# Schematic.net
KiCad netlist of a schematic drawn in Altium Designer
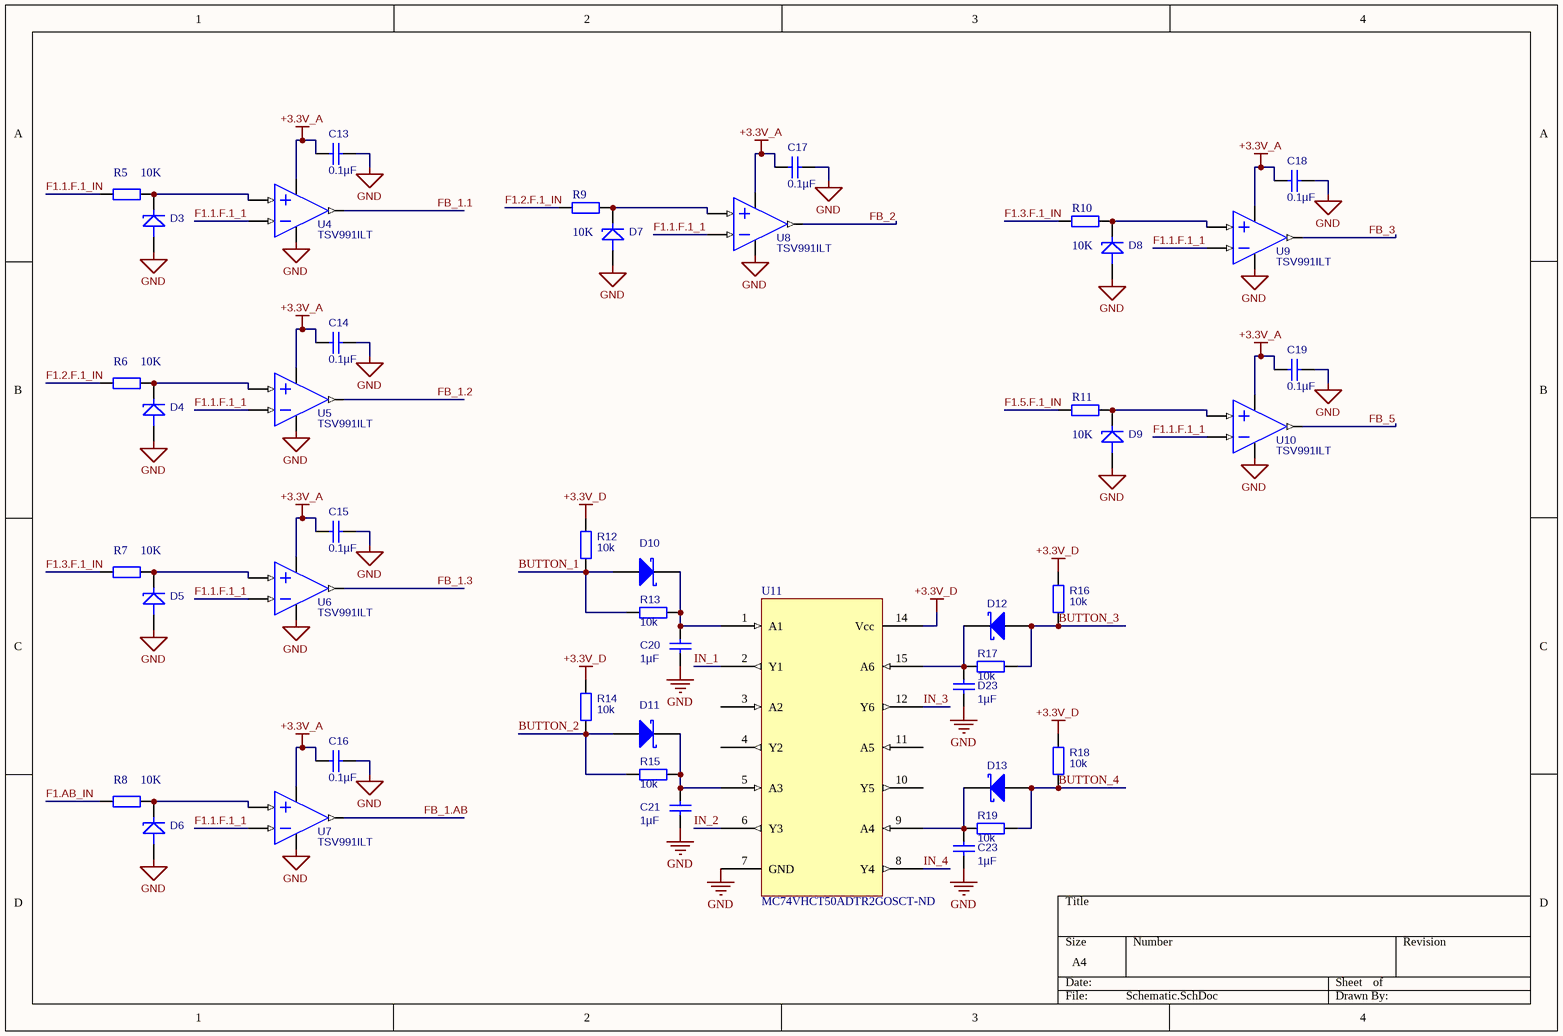
[diagram p0: Schematic.SchDoc]

(export (version "E")
  (design (tool "Eeschema 10.0.6"))
  (components
    (comp (ref "C13")
      (value "0.1µF")
      (footprint "TDK C-Series (1608)")
      (description "Capacitor")
      (fields (field (name "PUBLISHER") "Altium Limited"))
      (libsource (lib "Miscellaneous Devices") (part "Cap"))
    )
    (comp (ref "C14")
      (value "0.1µF")
      (footprint "TDK C-Series (1608)")
      (description "Capacitor")
      (fields (field (name "PUBLISHER") "Altium Limited"))
      (libsource (lib "Miscellaneous Devices") (part "Cap"))
    )
    (comp (ref "C15")
      (value "0.1µF")
      (footprint "TDK C-Series (1608)")
      (description "Capacitor")
      (fields (field (name "PUBLISHER") "Altium Limited"))
      (libsource (lib "Miscellaneous Devices") (part "Cap"))
    )
    (comp (ref "C16")
      (value "0.1µF")
      (footprint "TDK C-Series (1608)")
      (description "Capacitor")
      (fields (field (name "PUBLISHER") "Altium Limited"))
      (libsource (lib "Miscellaneous Devices") (part "Cap"))
    )
    (comp (ref "C17")
      (value "0.1µF")
      (footprint "TDK C-Series (1608)")
      (description "Capacitor")
      (fields (field (name "PUBLISHER") "Altium Limited"))
      (libsource (lib "Miscellaneous Devices") (part "Cap"))
    )
    (comp (ref "C18")
      (value "0.1µF")
      (footprint "TDK C-Series (1608)")
      (description "Capacitor")
      (fields (field (name "PUBLISHER") "Altium Limited"))
      (libsource (lib "Miscellaneous Devices") (part "Cap"))
    )
    (comp (ref "C19")
      (value "0.1µF")
      (footprint "TDK C-Series (1608)")
      (description "Capacitor")
      (fields (field (name "PUBLISHER") "Altium Limited"))
      (libsource (lib "Miscellaneous Devices") (part "Cap"))
    )
    (comp (ref "C20")
      (value "1µF")
      (footprint "TDK C-Series (1608)")
      (description "Capacitor")
      (fields (field (name "Comment") "Cap") (field (name "PUBLISHER") "Altium Limited"))
      (libsource (lib "Miscellaneous Devices") (part "Cap"))
    )
    (comp (ref "C21")
      (value "1µF")
      (footprint "TDK C-Series (1608)")
      (description "Capacitor")
      (fields (field (name "Comment") "Cap") (field (name "PUBLISHER") "Altium Limited"))
      (libsource (lib "Miscellaneous Devices") (part "Cap"))
    )
    (comp (ref "C23")
      (value "1µF")
      (footprint "TDK C-Series (1608)")
      (description "Capacitor")
      (fields (field (name "Comment") "Cap") (field (name "PUBLISHER") "Altium Limited"))
      (libsource (lib "Miscellaneous Devices") (part "Cap"))
    )
    (comp (ref "D3")
      (value "PTVSxS1UR-Series")
      (footprint "NXP PTVSxS1UR-Series (SOD123W)")
      (description "400W TVS Diode")
      (libsource (lib "FSM_2017") (part "NXP PTVSxS1UR-Series"))
    )
    (comp (ref "D4")
      (value "PTVSxS1UR-Series")
      (footprint "NXP PTVSxS1UR-Series (SOD123W)")
      (description "400W TVS Diode")
      (libsource (lib "FSM_2017") (part "NXP PTVSxS1UR-Series"))
    )
    (comp (ref "D5")
      (value "PTVSxS1UR-Series")
      (footprint "NXP PTVSxS1UR-Series (SOD123W)")
      (description "400W TVS Diode")
      (libsource (lib "FSM_2017") (part "NXP PTVSxS1UR-Series"))
    )
    (comp (ref "D6")
      (value "PTVSxS1UR-Series")
      (footprint "NXP PTVSxS1UR-Series (SOD123W)")
      (description "400W TVS Diode")
      (libsource (lib "FSM_2017") (part "NXP PTVSxS1UR-Series"))
    )
    (comp (ref "D7")
      (value "PTVSxS1UR-Series")
      (footprint "NXP PTVSxS1UR-Series (SOD123W)")
      (description "400W TVS Diode")
      (libsource (lib "FSM_2017") (part "NXP PTVSxS1UR-Series"))
    )
    (comp (ref "D8")
      (value "PTVSxS1UR-Series")
      (footprint "NXP PTVSxS1UR-Series (SOD123W)")
      (description "400W TVS Diode")
      (libsource (lib "FSM_2017") (part "NXP PTVSxS1UR-Series"))
    )
    (comp (ref "D9")
      (value "PTVSxS1UR-Series")
      (footprint "NXP PTVSxS1UR-Series (SOD123W)")
      (description "400W TVS Diode")
      (libsource (lib "FSM_2017") (part "NXP PTVSxS1UR-Series"))
    )
    (comp (ref "D10")
      (value "D Schottky")
      (footprint "NXP PMEG6020AELRX (SOD-123)")
      (description "Schottky Diode")
      (fields (field (name "PUBLISHER") "Altium Limited"))
      (libsource (lib "Miscellaneous Devices") (part "D Schottky"))
    )
    (comp (ref "D11")
      (value "D Schottky")
      (footprint "NXP PMEG6020AELRX (SOD-123)")
      (description "Schottky Diode")
      (fields (field (name "PUBLISHER") "Altium Limited"))
      (libsource (lib "Miscellaneous Devices") (part "D Schottky"))
    )
    (comp (ref "D12")
      (value "D Schottky")
      (footprint "NXP PMEG6020AELRX (SOD-123)")
      (description "Schottky Diode")
      (fields (field (name "PUBLISHER") "Altium Limited"))
      (libsource (lib "Miscellaneous Devices") (part "D Schottky"))
    )
    (comp (ref "D13")
      (value "D Schottky")
      (footprint "NXP PMEG6020AELRX (SOD-123)")
      (description "Schottky Diode")
      (fields (field (name "PUBLISHER") "Altium Limited"))
      (libsource (lib "Miscellaneous Devices") (part "D Schottky"))
    )
    (comp (ref "D23")
      (value "1µF")
      (footprint "TDK C-Series (1608)")
      (description "Capacitor")
      (fields (field (name "Comment") "Cap") (field (name "PUBLISHER") "Altium Limited"))
      (libsource (lib "Miscellaneous Devices") (part "Cap"))
    )
    (comp (ref "R5")
      (value "10K")
      (footprint "AXIAL-0.4")
      (description "Resistor")
      (fields (field (name "PUBLISHER") "Altium Limited"))
      (libsource (lib "Miscellaneous Devices") (part "Res2"))
    )
    (comp (ref "R6")
      (value "10K")
      (footprint "AXIAL-0.4")
      (description "Resistor")
      (fields (field (name "PUBLISHER") "Altium Limited"))
      (libsource (lib "Miscellaneous Devices") (part "Res2"))
    )
    (comp (ref "R7")
      (value "10K")
      (footprint "AXIAL-0.4")
      (description "Resistor")
      (fields (field (name "PUBLISHER") "Altium Limited"))
      (libsource (lib "Miscellaneous Devices") (part "Res2"))
    )
    (comp (ref "R8")
      (value "10K")
      (footprint "AXIAL-0.4")
      (description "Resistor")
      (fields (field (name "PUBLISHER") "Altium Limited"))
      (libsource (lib "Miscellaneous Devices") (part "Res2"))
    )
    (comp (ref "R9")
      (value "10K")
      (footprint "AXIAL-0.4")
      (description "Resistor")
      (fields (field (name "PUBLISHER") "Altium Limited"))
      (libsource (lib "Miscellaneous Devices") (part "Res2"))
    )
    (comp (ref "R10")
      (value "10K")
      (footprint "AXIAL-0.4")
      (description "Resistor")
      (fields (field (name "PUBLISHER") "Altium Limited"))
      (libsource (lib "Miscellaneous Devices") (part "Res2"))
    )
    (comp (ref "R11")
      (value "10K")
      (footprint "AXIAL-0.4")
      (description "Resistor")
      (fields (field (name "PUBLISHER") "Altium Limited"))
      (libsource (lib "Miscellaneous Devices") (part "Res2"))
    )
    (comp (ref "R12")
      (value "10k")
      (footprint "Panasonic ERJ-Series (1608)")
      (description "Resistor")
      (fields (field (name "PUBLISHER") "Altium Limited"))
      (libsource (lib "Miscellaneous Devices") (part "Res2"))
    )
    (comp (ref "R13")
      (value "10k")
      (footprint "Panasonic ERJ-Series (1608)")
      (description "Resistor")
      (fields (field (name "PUBLISHER") "Altium Limited"))
      (libsource (lib "") (part "Res2_1"))
    )
    (comp (ref "R14")
      (value "10k")
      (footprint "Panasonic ERJ-Series (1608)")
      (description "Resistor")
      (fields (field (name "PUBLISHER") "Altium Limited"))
      (libsource (lib "Miscellaneous Devices") (part "Res2"))
    )
    (comp (ref "R15")
      (value "10k")
      (footprint "Panasonic ERJ-Series (1608)")
      (description "Resistor")
      (fields (field (name "PUBLISHER") "Altium Limited"))
      (libsource (lib "") (part "Res2_1"))
    )
    (comp (ref "R16")
      (value "10k")
      (footprint "Panasonic ERJ-Series (1608)")
      (description "Resistor")
      (fields (field (name "PUBLISHER") "Altium Limited"))
      (libsource (lib "Miscellaneous Devices") (part "Res2"))
    )
    (comp (ref "R17")
      (value "10k")
      (footprint "Panasonic ERJ-Series (1608)")
      (description "Resistor")
      (fields (field (name "PUBLISHER") "Altium Limited"))
      (libsource (lib "") (part "Res2_1"))
    )
    (comp (ref "R18")
      (value "10k")
      (footprint "Panasonic ERJ-Series (1608)")
      (description "Resistor")
      (fields (field (name "PUBLISHER") "Altium Limited"))
      (libsource (lib "Miscellaneous Devices") (part "Res2"))
    )
    (comp (ref "R19")
      (value "10k")
      (footprint "Panasonic ERJ-Series (1608)")
      (description "Resistor")
      (fields (field (name "PUBLISHER") "Altium Limited"))
      (libsource (lib "") (part "Res2_1"))
    )
    (comp (ref "U4")
      (value "TSV991ILT")
      (footprint "STMicroelectronics TSV991ILT (SOT-23-5)")
      (description "20MHz Op-Amp")
      (libsource (lib "FSM_2017") (part "STMicroelectronics TSV991ILT"))
    )
    (comp (ref "U5")
      (value "TSV991ILT")
      (footprint "STMicroelectronics TSV991ILT (SOT-23-5)")
      (description "20MHz Op-Amp")
      (libsource (lib "FSM_2017") (part "STMicroelectronics TSV991ILT"))
    )
    (comp (ref "U6")
      (value "TSV991ILT")
      (footprint "STMicroelectronics TSV991ILT (SOT-23-5)")
      (description "20MHz Op-Amp")
      (libsource (lib "FSM_2017") (part "STMicroelectronics TSV991ILT"))
    )
    (comp (ref "U7")
      (value "TSV991ILT")
      (footprint "STMicroelectronics TSV991ILT (SOT-23-5)")
      (description "20MHz Op-Amp")
      (libsource (lib "FSM_2017") (part "STMicroelectronics TSV991ILT"))
    )
    (comp (ref "U8")
      (value "TSV991ILT")
      (footprint "STMicroelectronics TSV991ILT (SOT-23-5)")
      (description "20MHz Op-Amp")
      (libsource (lib "FSM_2017") (part "STMicroelectronics TSV991ILT"))
    )
    (comp (ref "U9")
      (value "TSV991ILT")
      (footprint "STMicroelectronics TSV991ILT (SOT-23-5)")
      (description "20MHz Op-Amp")
      (libsource (lib "FSM_2017") (part "STMicroelectronics TSV991ILT"))
    )
    (comp (ref "U10")
      (value "TSV991ILT")
      (footprint "STMicroelectronics TSV991ILT (SOT-23-5)")
      (description "20MHz Op-Amp")
      (libsource (lib "FSM_2017") (part "STMicroelectronics TSV991ILT"))
    )
    (comp (ref "U11")
      (value "MC74VHCT50A")
      (description "6-Channel CMOS Buffer")
      (fields (field (name "SUPPLIER PART NUMBER 1") "MC74VHCT50ADTR2GOSCT-ND"))
      (libsource (lib "Schematics Library") (part "MC74VHCT50A"))
    )
  )
  (nets
    (net (code "1") (name "+3.3V_A") (class "Default")
      (node (ref "C13") (pin "2") (pinfunction "2_2") (pintype "passive"))
      (node (ref "C14") (pin "2") (pinfunction "2_2") (pintype "passive"))
      (node (ref "C15") (pin "2") (pinfunction "2_2") (pintype "passive"))
      (node (ref "C16") (pin "2") (pinfunction "2_2") (pintype "passive"))
      (node (ref "C17") (pin "2") (pinfunction "2_2") (pintype "passive"))
      (node (ref "C18") (pin "2") (pinfunction "2_2") (pintype "passive"))
      (node (ref "C19") (pin "2") (pinfunction "2_2") (pintype "passive"))
      (node (ref "U10") (pin "5") (pinfunction "VCC+_5") (pintype "power_in"))
      (node (ref "U4") (pin "5") (pinfunction "VCC+_5") (pintype "power_in"))
      (node (ref "U5") (pin "5") (pinfunction "VCC+_5") (pintype "power_in"))
      (node (ref "U6") (pin "5") (pinfunction "VCC+_5") (pintype "power_in"))
      (node (ref "U7") (pin "5") (pinfunction "VCC+_5") (pintype "power_in"))
      (node (ref "U8") (pin "5") (pinfunction "VCC+_5") (pintype "power_in"))
      (node (ref "U9") (pin "5") (pinfunction "VCC+_5") (pintype "power_in"))
    )
    (net (code "2") (name "+3.3V_D") (class "Default")
      (node (ref "R12") (pin "1") (pinfunction "1_1") (pintype "passive"))
      (node (ref "R14") (pin "1") (pinfunction "1_1") (pintype "passive"))
      (node (ref "R16") (pin "1") (pinfunction "1_1") (pintype "passive"))
      (node (ref "R18") (pin "1") (pinfunction "1_1") (pintype "passive"))
      (node (ref "U11") (pin "14") (pinfunction "Vcc_14") (pintype "power_in"))
    )
    (net (code "3") (name "/BUTTON_1") (class "Default")
      (node (ref "D10") (pin "1") (pinfunction "A_1") (pintype "passive"))
      (node (ref "R12") (pin "2") (pinfunction "2_2") (pintype "passive"))
      (node (ref "R13") (pin "1") (pinfunction "1_1") (pintype "passive"))
    )
    (net (code "4") (name "/BUTTON_2") (class "Default")
      (node (ref "D11") (pin "1") (pinfunction "A_1") (pintype "passive"))
      (node (ref "R14") (pin "2") (pinfunction "2_2") (pintype "passive"))
      (node (ref "R15") (pin "1") (pinfunction "1_1") (pintype "passive"))
    )
    (net (code "5") (name "/BUTTON_3") (class "Default")
      (node (ref "D12") (pin "1") (pinfunction "A_1") (pintype "passive"))
      (node (ref "R16") (pin "2") (pinfunction "2_2") (pintype "passive"))
      (node (ref "R17") (pin "2") (pinfunction "2_2") (pintype "passive"))
    )
    (net (code "6") (name "/BUTTON_4") (class "Default")
      (node (ref "D13") (pin "1") (pinfunction "A_1") (pintype "passive"))
      (node (ref "R18") (pin "2") (pinfunction "2_2") (pintype "passive"))
      (node (ref "R19") (pin "2") (pinfunction "2_2") (pintype "passive"))
    )
    (net (code "7") (name "/F1.1.F.1_1") (class "Default")
      (node (ref "U10") (pin "4") (pinfunction "IN-_4") (pintype "input"))
      (node (ref "U4") (pin "4") (pinfunction "IN-_4") (pintype "input"))
      (node (ref "U5") (pin "4") (pinfunction "IN-_4") (pintype "input"))
      (node (ref "U6") (pin "4") (pinfunction "IN-_4") (pintype "input"))
      (node (ref "U7") (pin "4") (pinfunction "IN-_4") (pintype "input"))
      (node (ref "U8") (pin "4") (pinfunction "IN-_4") (pintype "input"))
      (node (ref "U9") (pin "4") (pinfunction "IN-_4") (pintype "input"))
    )
    (net (code "8") (name "/F1.1.F.1_IN") (class "Default")
      (node (ref "R5") (pin "2") (pinfunction "2_2") (pintype "passive"))
    )
    (net (code "9") (name "/F1.2.F.1_IN") (class "Default")
      (node (ref "R6") (pin "2") (pinfunction "2_2") (pintype "passive"))
      (node (ref "R9") (pin "2") (pinfunction "2_2") (pintype "passive"))
    )
    (net (code "10") (name "/F1.3.F.1_IN") (class "Default")
      (node (ref "R10") (pin "2") (pinfunction "2_2") (pintype "passive"))
      (node (ref "R7") (pin "2") (pinfunction "2_2") (pintype "passive"))
    )
    (net (code "11") (name "/F1.5.F.1_IN") (class "Default")
      (node (ref "R11") (pin "2") (pinfunction "2_2") (pintype "passive"))
    )
    (net (code "12") (name "/F1.AB_IN") (class "Default")
      (node (ref "R8") (pin "2") (pinfunction "2_2") (pintype "passive"))
    )
    (net (code "13") (name "/FB_1.1") (class "Default")
      (node (ref "U4") (pin "1") (pinfunction "OUT_1") (pintype "output"))
    )
    (net (code "14") (name "/FB_1.2") (class "Default")
      (node (ref "U5") (pin "1") (pinfunction "OUT_1") (pintype "output"))
    )
    (net (code "15") (name "/FB_1.3") (class "Default")
      (node (ref "U6") (pin "1") (pinfunction "OUT_1") (pintype "output"))
    )
    (net (code "16") (name "/FB_1.AB") (class "Default")
      (node (ref "U7") (pin "1") (pinfunction "OUT_1") (pintype "output"))
    )
    (net (code "17") (name "/FB_2") (class "Default")
      (node (ref "U8") (pin "1") (pinfunction "OUT_1") (pintype "output"))
    )
    (net (code "18") (name "/FB_3") (class "Default")
      (node (ref "U9") (pin "1") (pinfunction "OUT_1") (pintype "output"))
    )
    (net (code "19") (name "/FB_5") (class "Default")
      (node (ref "U10") (pin "1") (pinfunction "OUT_1") (pintype "output"))
    )
    (net (code "20") (name "/IN_1") (class "Default")
      (node (ref "U11") (pin "2") (pinfunction "Y1_2") (pintype "output"))
    )
    (net (code "21") (name "/IN_2") (class "Default")
      (node (ref "U11") (pin "6") (pinfunction "Y3_6") (pintype "output"))
    )
    (net (code "22") (name "/IN_3") (class "Default")
      (node (ref "U11") (pin "12") (pinfunction "Y6_12") (pintype "output"))
    )
    (net (code "23") (name "/IN_4") (class "Default")
      (node (ref "U11") (pin "8") (pinfunction "Y4_8") (pintype "output"))
    )
    (net (code "24") (name "GND") (class "Default")
      (node (ref "C13") (pin "1") (pinfunction "1_1") (pintype "passive"))
      (node (ref "C14") (pin "1") (pinfunction "1_1") (pintype "passive"))
      (node (ref "C15") (pin "1") (pinfunction "1_1") (pintype "passive"))
      (node (ref "C16") (pin "1") (pinfunction "1_1") (pintype "passive"))
      (node (ref "C17") (pin "1") (pinfunction "1_1") (pintype "passive"))
      (node (ref "C18") (pin "1") (pinfunction "1_1") (pintype "passive"))
      (node (ref "C19") (pin "1") (pinfunction "1_1") (pintype "passive"))
      (node (ref "C20") (pin "1") (pinfunction "1_1") (pintype "passive"))
      (node (ref "C21") (pin "1") (pinfunction "1_1") (pintype "passive"))
      (node (ref "C23") (pin "1") (pinfunction "1_1") (pintype "passive"))
      (node (ref "D23") (pin "1") (pinfunction "1_1") (pintype "passive"))
      (node (ref "D3") (pin "2") (pinfunction "2_2") (pintype "passive"))
      (node (ref "D4") (pin "2") (pinfunction "2_2") (pintype "passive"))
      (node (ref "D5") (pin "2") (pinfunction "2_2") (pintype "passive"))
      (node (ref "D6") (pin "2") (pinfunction "2_2") (pintype "passive"))
      (node (ref "D7") (pin "2") (pinfunction "2_2") (pintype "passive"))
      (node (ref "D8") (pin "2") (pinfunction "2_2") (pintype "passive"))
      (node (ref "D9") (pin "2") (pinfunction "2_2") (pintype "passive"))
      (node (ref "U10") (pin "2") (pinfunction "VCC-_2") (pintype "power_in"))
      (node (ref "U11") (pin "7") (pinfunction "GND_7") (pintype "passive"))
      (node (ref "U4") (pin "2") (pinfunction "VCC-_2") (pintype "power_in"))
      (node (ref "U5") (pin "2") (pinfunction "VCC-_2") (pintype "power_in"))
      (node (ref "U6") (pin "2") (pinfunction "VCC-_2") (pintype "power_in"))
      (node (ref "U7") (pin "2") (pinfunction "VCC-_2") (pintype "power_in"))
      (node (ref "U8") (pin "2") (pinfunction "VCC-_2") (pintype "power_in"))
      (node (ref "U9") (pin "2") (pinfunction "VCC-_2") (pintype "power_in"))
    )
    (net (code "25") (name "Net-(D10-K)") (class "Default")
      (node (ref "C20") (pin "2") (pinfunction "2_2") (pintype "passive"))
      (node (ref "D10") (pin "2") (pinfunction "K_2") (pintype "passive"))
      (node (ref "R13") (pin "2") (pinfunction "2_2") (pintype "passive"))
      (node (ref "U11") (pin "1") (pinfunction "A1_1") (pintype "input"))
    )
    (net (code "26") (name "Net-(D11-K)") (class "Default")
      (node (ref "C21") (pin "2") (pinfunction "2_2") (pintype "passive"))
      (node (ref "D11") (pin "2") (pinfunction "K_2") (pintype "passive"))
      (node (ref "R15") (pin "2") (pinfunction "2_2") (pintype "passive"))
      (node (ref "U11") (pin "5") (pinfunction "A3_5") (pintype "input"))
    )
    (net (code "27") (name "Net-(D12-K)") (class "Default")
      (node (ref "D12") (pin "2") (pinfunction "K_2") (pintype "passive"))
      (node (ref "D23") (pin "2") (pinfunction "2_2") (pintype "passive"))
      (node (ref "R17") (pin "1") (pinfunction "1_1") (pintype "passive"))
      (node (ref "U11") (pin "15") (pinfunction "A6_15") (pintype "input"))
    )
    (net (code "28") (name "Net-(D13-K)") (class "Default")
      (node (ref "C23") (pin "2") (pinfunction "2_2") (pintype "passive"))
      (node (ref "D13") (pin "2") (pinfunction "K_2") (pintype "passive"))
      (node (ref "R19") (pin "1") (pinfunction "1_1") (pintype "passive"))
      (node (ref "U11") (pin "9") (pinfunction "A4_9") (pintype "input"))
    )
    (net (code "29") (name "Net-(U4-IN+)") (class "Default")
      (node (ref "D3") (pin "1") (pinfunction "1_1") (pintype "passive"))
      (node (ref "R5") (pin "1") (pinfunction "1_1") (pintype "passive"))
      (node (ref "U4") (pin "3") (pinfunction "IN+_3") (pintype "input"))
    )
    (net (code "30") (name "Net-(U5-IN+)") (class "Default")
      (node (ref "D4") (pin "1") (pinfunction "1_1") (pintype "passive"))
      (node (ref "R6") (pin "1") (pinfunction "1_1") (pintype "passive"))
      (node (ref "U5") (pin "3") (pinfunction "IN+_3") (pintype "input"))
    )
    (net (code "31") (name "Net-(U6-IN+)") (class "Default")
      (node (ref "D5") (pin "1") (pinfunction "1_1") (pintype "passive"))
      (node (ref "R7") (pin "1") (pinfunction "1_1") (pintype "passive"))
      (node (ref "U6") (pin "3") (pinfunction "IN+_3") (pintype "input"))
    )
    (net (code "32") (name "Net-(U7-IN+)") (class "Default")
      (node (ref "D6") (pin "1") (pinfunction "1_1") (pintype "passive"))
      (node (ref "R8") (pin "1") (pinfunction "1_1") (pintype "passive"))
      (node (ref "U7") (pin "3") (pinfunction "IN+_3") (pintype "input"))
    )
    (net (code "33") (name "Net-(U8-IN+)") (class "Default")
      (node (ref "D7") (pin "1") (pinfunction "1_1") (pintype "passive"))
      (node (ref "R9") (pin "1") (pinfunction "1_1") (pintype "passive"))
      (node (ref "U8") (pin "3") (pinfunction "IN+_3") (pintype "input"))
    )
    (net (code "34") (name "Net-(U9-IN+)") (class "Default")
      (node (ref "D8") (pin "1") (pinfunction "1_1") (pintype "passive"))
      (node (ref "R10") (pin "1") (pinfunction "1_1") (pintype "passive"))
      (node (ref "U9") (pin "3") (pinfunction "IN+_3") (pintype "input"))
    )
    (net (code "35") (name "Net-(U10-IN+)") (class "Default")
      (node (ref "D9") (pin "1") (pinfunction "1_1") (pintype "passive"))
      (node (ref "R11") (pin "1") (pinfunction "1_1") (pintype "passive"))
      (node (ref "U10") (pin "3") (pinfunction "IN+_3") (pintype "input"))
    )
    (net (code "36") (name "unconnected-(U11-A2-Pad3)") (class "Default")
      (node (ref "U11") (pin "3") (pinfunction "A2_3") (pintype "input"))
    )
    (net (code "37") (name "unconnected-(U11-A5-Pad11)") (class "Default")
      (node (ref "U11") (pin "11") (pinfunction "A5_11") (pintype "input"))
    )
    (net (code "38") (name "unconnected-(U11-Y2-Pad4)") (class "Default")
      (node (ref "U11") (pin "4") (pinfunction "Y2_4") (pintype "output"))
    )
    (net (code "39") (name "unconnected-(U11-Y5-Pad10)") (class "Default")
      (node (ref "U11") (pin "10") (pinfunction "Y5_10") (pintype "output"))
    )
  )
)
